# ATtinyBoard_3.net
KiCad netlist of a schematic drawn in EAGLE
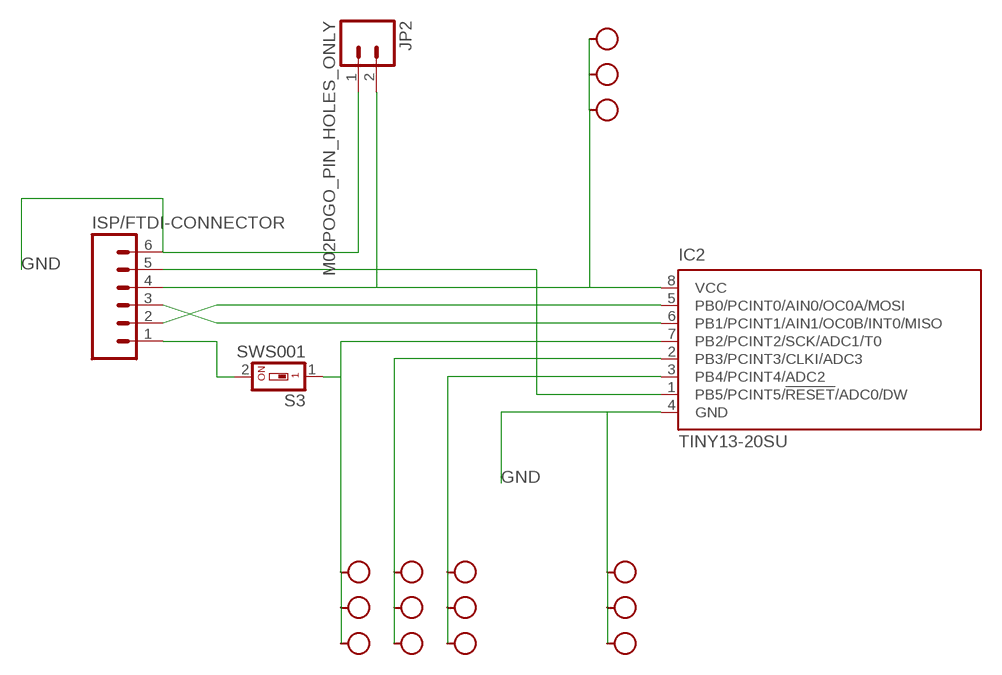
[diagram p0: schematic, sheet 1]

(export (version "E")
  (design (tool "Eeschema 10.0.6"))
  (components
    (comp (ref "H1")
      (value "SEW_HOLE-SMALL")
      (footprint "eagle-import:SIMPLE_HOLE_SM")
      (libsource (lib "eagle-import") (part "SEW_HOLE-SMALL"))
    )
    (comp (ref "H2")
      (value "SEW_HOLE-SMALL")
      (footprint "eagle-import:SIMPLE_HOLE_SM")
      (libsource (lib "eagle-import") (part "SEW_HOLE-SMALL"))
    )
    (comp (ref "H3")
      (value "SEW_HOLE-SMALL")
      (footprint "eagle-import:SIMPLE_HOLE_SM")
      (libsource (lib "eagle-import") (part "SEW_HOLE-SMALL"))
    )
    (comp (ref "H4")
      (value "SEW_HOLE-SMALL")
      (footprint "eagle-import:SIMPLE_HOLE_SM")
      (libsource (lib "eagle-import") (part "SEW_HOLE-SMALL"))
    )
    (comp (ref "H5")
      (value "SEW_HOLE-SMALL")
      (footprint "eagle-import:SIMPLE_HOLE_SM")
      (libsource (lib "eagle-import") (part "SEW_HOLE-SMALL"))
    )
    (comp (ref "H6")
      (value "SEW_HOLE-SMALL")
      (footprint "eagle-import:SIMPLE_HOLE_SM")
      (libsource (lib "eagle-import") (part "SEW_HOLE-SMALL"))
    )
    (comp (ref "H7")
      (value "SEW_HOLE-SMALL")
      (footprint "eagle-import:SIMPLE_HOLE_SM")
      (libsource (lib "eagle-import") (part "SEW_HOLE-SMALL"))
    )
    (comp (ref "H8")
      (value "SEW_HOLE-SMALL")
      (footprint "eagle-import:SIMPLE_HOLE_SM")
      (libsource (lib "eagle-import") (part "SEW_HOLE-SMALL"))
    )
    (comp (ref "H9")
      (value "SEW_HOLE-SMALL")
      (footprint "eagle-import:SIMPLE_HOLE_SM")
      (libsource (lib "eagle-import") (part "SEW_HOLE-SMALL"))
    )
    (comp (ref "H10")
      (value "SEW_HOLE-SMALL")
      (footprint "eagle-import:SIMPLE_HOLE_SM")
      (libsource (lib "eagle-import") (part "SEW_HOLE-SMALL"))
    )
    (comp (ref "H11")
      (value "SEW_HOLE-SMALL")
      (footprint "eagle-import:SIMPLE_HOLE_SM")
      (libsource (lib "eagle-import") (part "SEW_HOLE-SMALL"))
    )
    (comp (ref "H12")
      (value "SEW_HOLE-SMALL")
      (footprint "eagle-import:SIMPLE_HOLE_SM")
      (libsource (lib "eagle-import") (part "SEW_HOLE-SMALL"))
    )
    (comp (ref "H13")
      (value "SEW_HOLE-SMALL")
      (footprint "eagle-import:SIMPLE_HOLE_SM")
      (libsource (lib "eagle-import") (part "SEW_HOLE-SMALL"))
    )
    (comp (ref "H14")
      (value "SEW_HOLE-SMALL")
      (footprint "eagle-import:SIMPLE_HOLE_SM")
      (libsource (lib "eagle-import") (part "SEW_HOLE-SMALL"))
    )
    (comp (ref "H15")
      (value "SEW_HOLE-SMALL")
      (footprint "eagle-import:SIMPLE_HOLE_SM")
      (libsource (lib "eagle-import") (part "SEW_HOLE-SMALL"))
    )
    (comp (ref "IC2")
      (value "TINY13-20SU")
      (footprint "eagle-import:8S2")
      (fields (field (name "MPN") "ATTINY13-20SU"))
      (libsource (lib "eagle-import") (part "TINY13SU-20"))
    )
    (comp (ref "ISP/FTDI-CONNECTOR")
      (value "M06SMD")
      (footprint "eagle-import:1X06-SMD")
      (libsource (lib "eagle-import") (part "M06SMD"))
    )
    (comp (ref "JP2")
      (value "M02POGO_PIN_HOLES_ONLY")
      (footprint "eagle-import:1X02_PP_HOLES_ONLY")
      (libsource (lib "eagle-import") (part "M02POGO_PIN_HOLES_ONLY"))
    )
    (comp (ref "S3")
      (value "SWS001")
      (footprint "eagle-import:SMS-001")
      (libsource (lib "eagle-import") (part "SWS001"))
    )
  )
  (nets
    (net (code "1") (name "/GND") (class "Default")
      (node (ref "H14") (pin "P$1") (pinfunction "P$1_P$1") (pintype "bidirectional"))
      (node (ref "H15") (pin "P$1") (pinfunction "P$1_P$1") (pintype "bidirectional"))
      (node (ref "H4") (pin "P$1") (pinfunction "P$1_P$1") (pintype "bidirectional"))
      (node (ref "IC2") (pin "4") (pinfunction "GND_4") (pintype "power_in"))
      (node (ref "ISP/FTDI-CONNECTOR") (pin "6") (pinfunction "6_6") (pintype "passive"))
      (node (ref "JP2") (pin "1") (pinfunction "1_1") (pintype "passive"))
    )
    (net (code "2") (name "Net-(IC2-PB0{slash}PCINT0{slash}AIN0{slash}OC0A{slash}MOSI)") (class "Default")
      (node (ref "IC2") (pin "5") (pinfunction "PB0/PCINT0/AIN0/OC0A/MOSI_5") (pintype "bidirectional"))
      (node (ref "ISP/FTDI-CONNECTOR") (pin "2") (pinfunction "2_2") (pintype "passive"))
    )
    (net (code "3") (name "Net-(IC2-PB1{slash}PCINT1{slash}AIN1{slash}OC0B{slash}INT0{slash}MISO)") (class "Default")
      (node (ref "IC2") (pin "6") (pinfunction "PB1/PCINT1/AIN1/OC0B/INT0/MISO_6") (pintype "bidirectional"))
      (node (ref "ISP/FTDI-CONNECTOR") (pin "3") (pinfunction "3_3") (pintype "passive"))
    )
    (net (code "4") (name "Net-(IC2-PB2{slash}PCINT2{slash}SCK{slash}ADC1{slash}T0)") (class "Default")
      (node (ref "H1") (pin "P$1") (pinfunction "P$1_P$1") (pintype "bidirectional"))
      (node (ref "H12") (pin "P$1") (pinfunction "P$1_P$1") (pintype "bidirectional"))
      (node (ref "H13") (pin "P$1") (pinfunction "P$1_P$1") (pintype "bidirectional"))
      (node (ref "IC2") (pin "7") (pinfunction "PB2/PCINT2/SCK/ADC1/T0_7") (pintype "bidirectional"))
      (node (ref "S3") (pin "1") (pinfunction "1_1") (pintype "passive"))
    )
    (net (code "5") (name "Net-(IC2-PB3{slash}PCINT3{slash}CLKI{slash}ADC3)") (class "Default")
      (node (ref "H10") (pin "P$1") (pinfunction "P$1_P$1") (pintype "bidirectional"))
      (node (ref "H11") (pin "P$1") (pinfunction "P$1_P$1") (pintype "bidirectional"))
      (node (ref "H2") (pin "P$1") (pinfunction "P$1_P$1") (pintype "bidirectional"))
      (node (ref "IC2") (pin "2") (pinfunction "PB3/PCINT3/CLKI/ADC3_2") (pintype "bidirectional"))
    )
    (net (code "6") (name "Net-(IC2-PB4{slash}PCINT4{slash}ADC2)") (class "Default")
      (node (ref "H3") (pin "P$1") (pinfunction "P$1_P$1") (pintype "bidirectional"))
      (node (ref "H8") (pin "P$1") (pinfunction "P$1_P$1") (pintype "bidirectional"))
      (node (ref "H9") (pin "P$1") (pinfunction "P$1_P$1") (pintype "bidirectional"))
      (node (ref "IC2") (pin "3") (pinfunction "PB4/PCINT4/ADC2_3") (pintype "bidirectional"))
    )
    (net (code "7") (name "Net-(IC2-PB5{slash}PCINT5{slash}~{RESET}{slash}ADC0{slash}DW)") (class "Default")
      (node (ref "IC2") (pin "1") (pinfunction "PB5/PCINT5/~{RESET}/ADC0/DW_1") (pintype "bidirectional"))
      (node (ref "ISP/FTDI-CONNECTOR") (pin "5") (pinfunction "5_5") (pintype "passive"))
    )
    (net (code "8") (name "Net-(IC2-VCC)") (class "Default")
      (node (ref "H5") (pin "P$1") (pinfunction "P$1_P$1") (pintype "bidirectional"))
      (node (ref "H6") (pin "P$1") (pinfunction "P$1_P$1") (pintype "bidirectional"))
      (node (ref "H7") (pin "P$1") (pinfunction "P$1_P$1") (pintype "bidirectional"))
      (node (ref "IC2") (pin "8") (pinfunction "VCC_8") (pintype "power_in"))
      (node (ref "ISP/FTDI-CONNECTOR") (pin "4") (pinfunction "4_4") (pintype "passive"))
      (node (ref "JP2") (pin "2") (pinfunction "2_2") (pintype "passive"))
    )
    (net (code "9") (name "Net-(ISP/FTDI-CONNECTOR-Pad1)") (class "Default")
      (node (ref "ISP/FTDI-CONNECTOR") (pin "1") (pinfunction "1_1") (pintype "passive"))
      (node (ref "S3") (pin "2") (pinfunction "2_2") (pintype "passive"))
    )
  )
)
